# vu.net
KiCad netlist of a schematic drawn in EAGLE
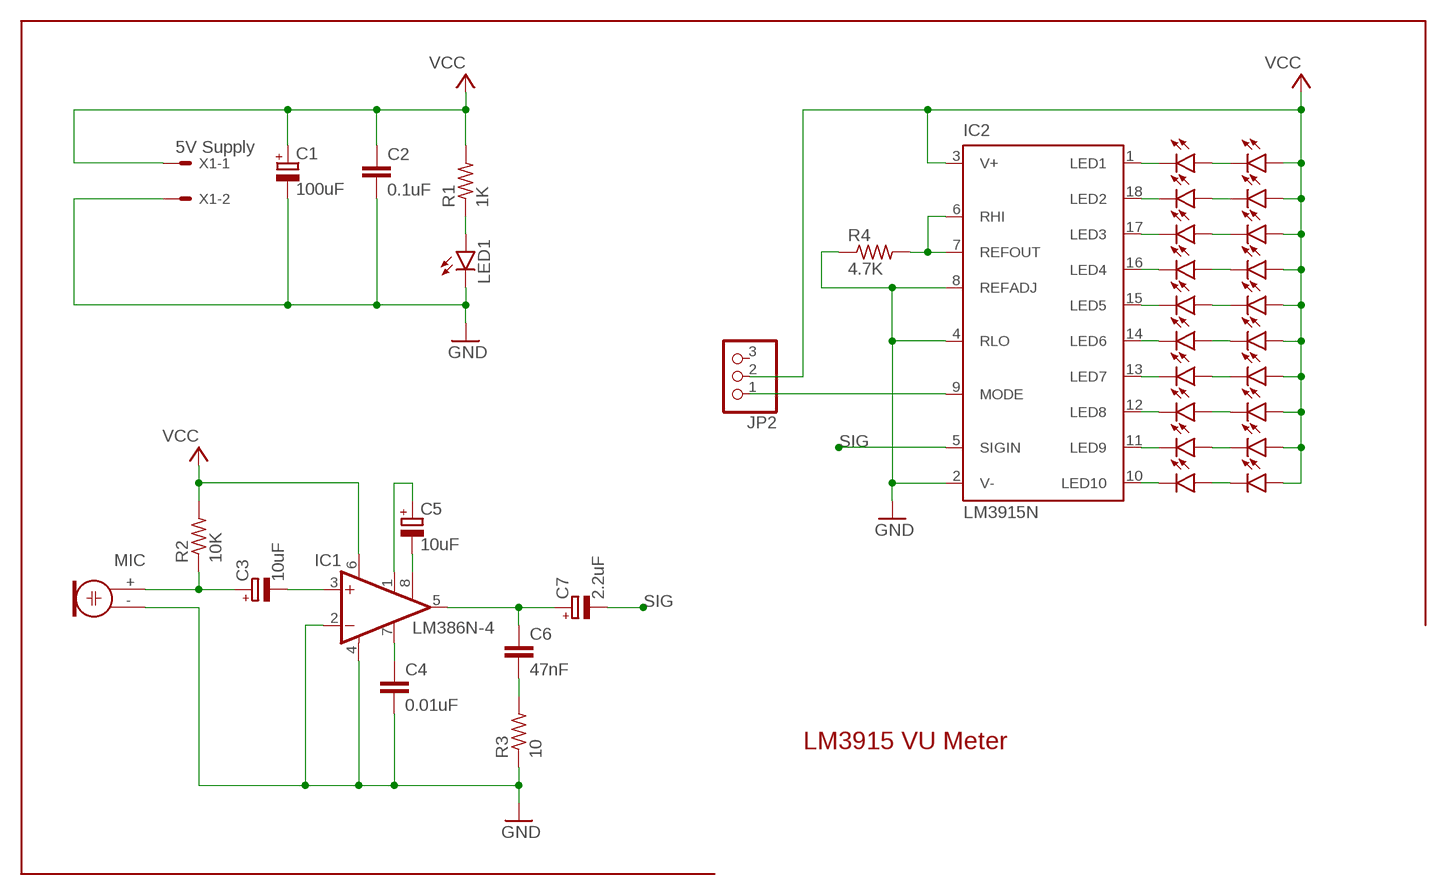
[diagram p0: schematic, sheet 1]

(export (version "E")
  (design (tool "Eeschema 10.0.6"))
  (components
    (comp (ref "C1")
      (value "100uF")
      (footprint "eagle-import:E2,5-6")
      (libsource (lib "eagle-import") (part "CPOL-EUE2.5-6"))
    )
    (comp (ref "C2")
      (value "0.1uF")
      (footprint "eagle-import:C025-050X050")
      (libsource (lib "eagle-import") (part "C-EU025-050X050"))
    )
    (comp (ref "C3")
      (value "10uF")
      (footprint "eagle-import:E2,5-6")
      (libsource (lib "eagle-import") (part "CPOL-EUE2.5-6"))
    )
    (comp (ref "C4")
      (value "0.01uF")
      (footprint "eagle-import:C050-024X044")
      (libsource (lib "eagle-import") (part "C-EU050-024X044"))
    )
    (comp (ref "C5")
      (value "10uF")
      (footprint "eagle-import:E2,5-6")
      (libsource (lib "eagle-import") (part "CPOL-EUE2.5-6"))
    )
    (comp (ref "C6")
      (value "47nF")
      (footprint "eagle-import:C025-050X050")
      (libsource (lib "eagle-import") (part "C-EU025-050X050"))
    )
    (comp (ref "C7")
      (value "2.2uF")
      (footprint "eagle-import:E5-6")
      (libsource (lib "eagle-import") (part "CPOL-EUE5-6"))
    )
    (comp (ref "IC1")
      (value "LM386N-4")
      (footprint "eagle-import:DIL08")
      (libsource (lib "eagle-import") (part "LM386?-N4"))
    )
    (comp (ref "IC2")
      (value "LM3915N")
      (footprint "eagle-import:DIL18")
      (libsource (lib "eagle-import") (part "LM391N5"))
    )
    (comp (ref "JP2")
      (value "PINHD-1X3")
      (footprint "eagle-import:1X03")
      (libsource (lib "eagle-import") (part "PINHD-1X3"))
    )
    (comp (ref "LED1")
      (value "LED5MM")
      (footprint "eagle-import:LED5MM")
      (libsource (lib "eagle-import") (part "LED5MM"))
    )
    (comp (ref "LED2")
      (value "LED5MM")
      (footprint "eagle-import:LED5MM")
      (libsource (lib "eagle-import") (part "LED5MM"))
    )
    (comp (ref "LED3")
      (value "LED5MM")
      (footprint "eagle-import:LED5MM")
      (libsource (lib "eagle-import") (part "LED5MM"))
    )
    (comp (ref "LED4")
      (value "LED5MM")
      (footprint "eagle-import:LED5MM")
      (libsource (lib "eagle-import") (part "LED5MM"))
    )
    (comp (ref "LED5")
      (value "LED5MM")
      (footprint "eagle-import:LED5MM")
      (libsource (lib "eagle-import") (part "LED5MM"))
    )
    (comp (ref "LED6")
      (value "LED5MM")
      (footprint "eagle-import:LED5MM")
      (libsource (lib "eagle-import") (part "LED5MM"))
    )
    (comp (ref "LED7")
      (value "LED5MM")
      (footprint "eagle-import:LED5MM")
      (libsource (lib "eagle-import") (part "LED5MM"))
    )
    (comp (ref "LED8")
      (value "LED5MM")
      (footprint "eagle-import:LED5MM")
      (libsource (lib "eagle-import") (part "LED5MM"))
    )
    (comp (ref "LED9")
      (value "LED5MM")
      (footprint "eagle-import:LED5MM")
      (libsource (lib "eagle-import") (part "LED5MM"))
    )
    (comp (ref "LED10")
      (value "LED5MM")
      (footprint "eagle-import:LED5MM")
      (libsource (lib "eagle-import") (part "LED5MM"))
    )
    (comp (ref "LED11")
      (value "LED5MM")
      (footprint "eagle-import:LED5MM")
      (libsource (lib "eagle-import") (part "LED5MM"))
    )
    (comp (ref "LED12")
      (value "LED5MM")
      (footprint "eagle-import:LED5MM")
      (libsource (lib "eagle-import") (part "LED5MM"))
    )
    (comp (ref "LED13")
      (value "LED5MM")
      (footprint "eagle-import:LED5MM")
      (libsource (lib "eagle-import") (part "LED5MM"))
    )
    (comp (ref "LED14")
      (value "LED5MM")
      (footprint "eagle-import:LED5MM")
      (libsource (lib "eagle-import") (part "LED5MM"))
    )
    (comp (ref "LED15")
      (value "LED5MM")
      (footprint "eagle-import:LED5MM")
      (libsource (lib "eagle-import") (part "LED5MM"))
    )
    (comp (ref "LED16")
      (value "LED5MM")
      (footprint "eagle-import:LED5MM")
      (libsource (lib "eagle-import") (part "LED5MM"))
    )
    (comp (ref "LED17")
      (value "LED5MM")
      (footprint "eagle-import:LED5MM")
      (libsource (lib "eagle-import") (part "LED5MM"))
    )
    (comp (ref "LED18")
      (value "LED5MM")
      (footprint "eagle-import:LED5MM")
      (libsource (lib "eagle-import") (part "LED5MM"))
    )
    (comp (ref "LED19")
      (value "LED5MM")
      (footprint "eagle-import:LED5MM")
      (libsource (lib "eagle-import") (part "LED5MM"))
    )
    (comp (ref "LED20")
      (value "LED5MM")
      (footprint "eagle-import:LED5MM")
      (libsource (lib "eagle-import") (part "LED5MM"))
    )
    (comp (ref "LED21")
      (value "LED5MM")
      (footprint "eagle-import:LED5MM")
      (libsource (lib "eagle-import") (part "LED5MM"))
    )
    (comp (ref "MIC")
      (value "ELECTRET")
      (footprint "eagle-import:9.7ELECTRET")
      (libsource (lib "eagle-import") (part "ELECTRET"))
    )
    (comp (ref "R1")
      (value "1K")
      (footprint "eagle-import:0207_10")
      (libsource (lib "eagle-import") (part "R-US_0207/10"))
    )
    (comp (ref "R2")
      (value "10K")
      (footprint "eagle-import:0207_10")
      (libsource (lib "eagle-import") (part "R-US_0207/10"))
    )
    (comp (ref "R3")
      (value "10")
      (footprint "eagle-import:0207_10")
      (libsource (lib "eagle-import") (part "R-US_0207/10"))
    )
    (comp (ref "R4")
      (value "4.7K")
      (footprint "eagle-import:0207_10")
      (libsource (lib "eagle-import") (part "R-US_0207/10"))
    )
    (comp (ref "X1")
      (value "5V Supply")
      (footprint "eagle-import:KK-156-2")
      (fields (field (name "MF") "MOLEX"))
      (libsource (lib "eagle-import") (part "KK-156-2"))
    )
  )
  (nets
    (net (code "1") (name "/SIG") (class "Default")
      (node (ref "C7") (pin "-") (pinfunction "-_-") (pintype "passive"))
      (node (ref "IC2") (pin "5") (pinfunction "SIGIN_5") (pintype "input"))
    )
    (net (code "2") (name "GND") (class "Default")
      (node (ref "C1") (pin "-") (pinfunction "-_-") (pintype "passive"))
      (node (ref "C2") (pin "2") (pinfunction "2_2") (pintype "passive"))
      (node (ref "C4") (pin "2") (pinfunction "2_2") (pintype "passive"))
      (node (ref "IC1") (pin "2") (pinfunction "-IN_2") (pintype "input"))
      (node (ref "IC1") (pin "4") (pinfunction "GND_4") (pintype "power_in"))
      (node (ref "IC2") (pin "2") (pinfunction "V-_2") (pintype "power_in"))
      (node (ref "IC2") (pin "4") (pinfunction "RLO_4") (pintype "input"))
      (node (ref "IC2") (pin "8") (pinfunction "REFADJ_8") (pintype "passive"))
      (node (ref "LED1") (pin "K") (pinfunction "C_K") (pintype "passive"))
      (node (ref "MIC") (pin "-") (pinfunction "1_-") (pintype "passive"))
      (node (ref "R3") (pin "1") (pinfunction "1_1") (pintype "passive"))
      (node (ref "R4") (pin "1") (pinfunction "1_1") (pintype "passive"))
      (node (ref "X1") (pin "2") (pinfunction "S_2") (pintype "passive"))
    )
    (net (code "3") (name "Net-(C5-Pad+)") (class "Default")
      (node (ref "C5") (pin "+") (pinfunction "+_+") (pintype "passive"))
      (node (ref "IC1") (pin "1") (pinfunction "GAIN_1") (pintype "passive"))
    )
    (net (code "4") (name "Net-(C5-Pad-)") (class "Default")
      (node (ref "C5") (pin "-") (pinfunction "-_-") (pintype "passive"))
      (node (ref "IC1") (pin "8") (pinfunction "GAIN_8") (pintype "passive"))
    )
    (net (code "5") (name "Net-(C6-Pad2)") (class "Default")
      (node (ref "C6") (pin "2") (pinfunction "2_2") (pintype "passive"))
      (node (ref "R3") (pin "2") (pinfunction "2_2") (pintype "passive"))
    )
    (net (code "6") (name "Net-(IC1-+IN)") (class "Default")
      (node (ref "C3") (pin "-") (pinfunction "-_-") (pintype "passive"))
      (node (ref "IC1") (pin "3") (pinfunction "+IN_3") (pintype "input"))
    )
    (net (code "7") (name "Net-(IC1-BYPASS)") (class "Default")
      (node (ref "C4") (pin "1") (pinfunction "1_1") (pintype "passive"))
      (node (ref "IC1") (pin "7") (pinfunction "BYPASS_7") (pintype "passive"))
    )
    (net (code "8") (name "Net-(IC1-OUT)") (class "Default")
      (node (ref "C6") (pin "1") (pinfunction "1_1") (pintype "passive"))
      (node (ref "C7") (pin "+") (pinfunction "+_+") (pintype "passive"))
      (node (ref "IC1") (pin "5") (pinfunction "OUT_5") (pintype "output"))
    )
    (net (code "9") (name "Net-(IC2-LED1)") (class "Default")
      (node (ref "IC2") (pin "1") (pinfunction "LED1_1") (pintype "output"))
      (node (ref "LED2") (pin "K") (pinfunction "C_K") (pintype "passive"))
    )
    (net (code "10") (name "Net-(IC2-LED2)") (class "Default")
      (node (ref "IC2") (pin "18") (pinfunction "LED2_18") (pintype "output"))
      (node (ref "LED4") (pin "K") (pinfunction "C_K") (pintype "passive"))
    )
    (net (code "11") (name "Net-(IC2-LED3)") (class "Default")
      (node (ref "IC2") (pin "17") (pinfunction "LED3_17") (pintype "output"))
      (node (ref "LED6") (pin "K") (pinfunction "C_K") (pintype "passive"))
    )
    (net (code "12") (name "Net-(IC2-LED4)") (class "Default")
      (node (ref "IC2") (pin "16") (pinfunction "LED4_16") (pintype "output"))
      (node (ref "LED8") (pin "K") (pinfunction "C_K") (pintype "passive"))
    )
    (net (code "13") (name "Net-(IC2-LED5)") (class "Default")
      (node (ref "IC2") (pin "15") (pinfunction "LED5_15") (pintype "output"))
      (node (ref "LED10") (pin "K") (pinfunction "C_K") (pintype "passive"))
    )
    (net (code "14") (name "Net-(IC2-LED6)") (class "Default")
      (node (ref "IC2") (pin "14") (pinfunction "LED6_14") (pintype "output"))
      (node (ref "LED12") (pin "K") (pinfunction "C_K") (pintype "passive"))
    )
    (net (code "15") (name "Net-(IC2-LED7)") (class "Default")
      (node (ref "IC2") (pin "13") (pinfunction "LED7_13") (pintype "output"))
      (node (ref "LED14") (pin "K") (pinfunction "C_K") (pintype "passive"))
    )
    (net (code "16") (name "Net-(IC2-LED8)") (class "Default")
      (node (ref "IC2") (pin "12") (pinfunction "LED8_12") (pintype "output"))
      (node (ref "LED16") (pin "K") (pinfunction "C_K") (pintype "passive"))
    )
    (net (code "17") (name "Net-(IC2-LED9)") (class "Default")
      (node (ref "IC2") (pin "11") (pinfunction "LED9_11") (pintype "output"))
      (node (ref "LED18") (pin "K") (pinfunction "C_K") (pintype "passive"))
    )
    (net (code "18") (name "Net-(IC2-LED10)") (class "Default")
      (node (ref "IC2") (pin "10") (pinfunction "LED10_10") (pintype "output"))
      (node (ref "LED20") (pin "K") (pinfunction "C_K") (pintype "passive"))
    )
    (net (code "19") (name "Net-(IC2-MODE)") (class "Default")
      (node (ref "IC2") (pin "9") (pinfunction "MODE_9") (pintype "input"))
      (node (ref "JP2") (pin "1") (pinfunction "1_1") (pintype "passive"))
    )
    (net (code "20") (name "Net-(IC2-REFOUT)") (class "Default")
      (node (ref "IC2") (pin "6") (pinfunction "RHI_6") (pintype "input"))
      (node (ref "IC2") (pin "7") (pinfunction "REFOUT_7") (pintype "output"))
      (node (ref "R4") (pin "2") (pinfunction "2_2") (pintype "passive"))
    )
    (net (code "21") (name "Net-(LED1-PadA)") (class "Default")
      (node (ref "LED1") (pin "A") (pinfunction "A_A") (pintype "passive"))
      (node (ref "R1") (pin "1") (pinfunction "1_1") (pintype "passive"))
    )
    (net (code "22") (name "Net-(LED3-C)") (class "Default")
      (node (ref "LED2") (pin "A") (pinfunction "A_A") (pintype "passive"))
      (node (ref "LED3") (pin "K") (pinfunction "C_K") (pintype "passive"))
    )
    (net (code "23") (name "Net-(LED5-C)") (class "Default")
      (node (ref "LED4") (pin "A") (pinfunction "A_A") (pintype "passive"))
      (node (ref "LED5") (pin "K") (pinfunction "C_K") (pintype "passive"))
    )
    (net (code "24") (name "Net-(LED7-C)") (class "Default")
      (node (ref "LED6") (pin "A") (pinfunction "A_A") (pintype "passive"))
      (node (ref "LED7") (pin "K") (pinfunction "C_K") (pintype "passive"))
    )
    (net (code "25") (name "Net-(LED9-C)") (class "Default")
      (node (ref "LED8") (pin "A") (pinfunction "A_A") (pintype "passive"))
      (node (ref "LED9") (pin "K") (pinfunction "C_K") (pintype "passive"))
    )
    (net (code "26") (name "Net-(LED11-C)") (class "Default")
      (node (ref "LED10") (pin "A") (pinfunction "A_A") (pintype "passive"))
      (node (ref "LED11") (pin "K") (pinfunction "C_K") (pintype "passive"))
    )
    (net (code "27") (name "Net-(LED13-C)") (class "Default")
      (node (ref "LED12") (pin "A") (pinfunction "A_A") (pintype "passive"))
      (node (ref "LED13") (pin "K") (pinfunction "C_K") (pintype "passive"))
    )
    (net (code "28") (name "Net-(LED15-C)") (class "Default")
      (node (ref "LED14") (pin "A") (pinfunction "A_A") (pintype "passive"))
      (node (ref "LED15") (pin "K") (pinfunction "C_K") (pintype "passive"))
    )
    (net (code "29") (name "Net-(LED17-C)") (class "Default")
      (node (ref "LED16") (pin "A") (pinfunction "A_A") (pintype "passive"))
      (node (ref "LED17") (pin "K") (pinfunction "C_K") (pintype "passive"))
    )
    (net (code "30") (name "Net-(LED19-C)") (class "Default")
      (node (ref "LED18") (pin "A") (pinfunction "A_A") (pintype "passive"))
      (node (ref "LED19") (pin "K") (pinfunction "C_K") (pintype "passive"))
    )
    (net (code "31") (name "Net-(LED21-C)") (class "Default")
      (node (ref "LED20") (pin "A") (pinfunction "A_A") (pintype "passive"))
      (node (ref "LED21") (pin "K") (pinfunction "C_K") (pintype "passive"))
    )
    (net (code "32") (name "Net-(MIC-2)") (class "Default")
      (node (ref "C3") (pin "+") (pinfunction "+_+") (pintype "passive"))
      (node (ref "MIC") (pin "+") (pinfunction "2_+") (pintype "passive"))
      (node (ref "R2") (pin "1") (pinfunction "1_1") (pintype "passive"))
    )
    (net (code "33") (name "VCC") (class "Default")
      (node (ref "C1") (pin "+") (pinfunction "+_+") (pintype "passive"))
      (node (ref "C2") (pin "1") (pinfunction "1_1") (pintype "passive"))
      (node (ref "IC1") (pin "6") (pinfunction "VS_6") (pintype "power_in"))
      (node (ref "IC2") (pin "3") (pinfunction "V+_3") (pintype "power_in"))
      (node (ref "JP2") (pin "2") (pinfunction "2_2") (pintype "passive"))
      (node (ref "LED11") (pin "A") (pinfunction "A_A") (pintype "passive"))
      (node (ref "LED13") (pin "A") (pinfunction "A_A") (pintype "passive"))
      (node (ref "LED15") (pin "A") (pinfunction "A_A") (pintype "passive"))
      (node (ref "LED17") (pin "A") (pinfunction "A_A") (pintype "passive"))
      (node (ref "LED19") (pin "A") (pinfunction "A_A") (pintype "passive"))
      (node (ref "LED21") (pin "A") (pinfunction "A_A") (pintype "passive"))
      (node (ref "LED3") (pin "A") (pinfunction "A_A") (pintype "passive"))
      (node (ref "LED5") (pin "A") (pinfunction "A_A") (pintype "passive"))
      (node (ref "LED7") (pin "A") (pinfunction "A_A") (pintype "passive"))
      (node (ref "LED9") (pin "A") (pinfunction "A_A") (pintype "passive"))
      (node (ref "R1") (pin "2") (pinfunction "2_2") (pintype "passive"))
      (node (ref "R2") (pin "2") (pinfunction "2_2") (pintype "passive"))
      (node (ref "X1") (pin "1") (pinfunction "S_1") (pintype "passive"))
    )
    (net (code "34") (name "unconnected-(JP2-Pad3)") (class "Default")
      (node (ref "JP2") (pin "3") (pinfunction "3_3") (pintype "passive"))
    )
  )
)
